# InputConn.net
KiCad netlist of a schematic drawn in Altium Designer
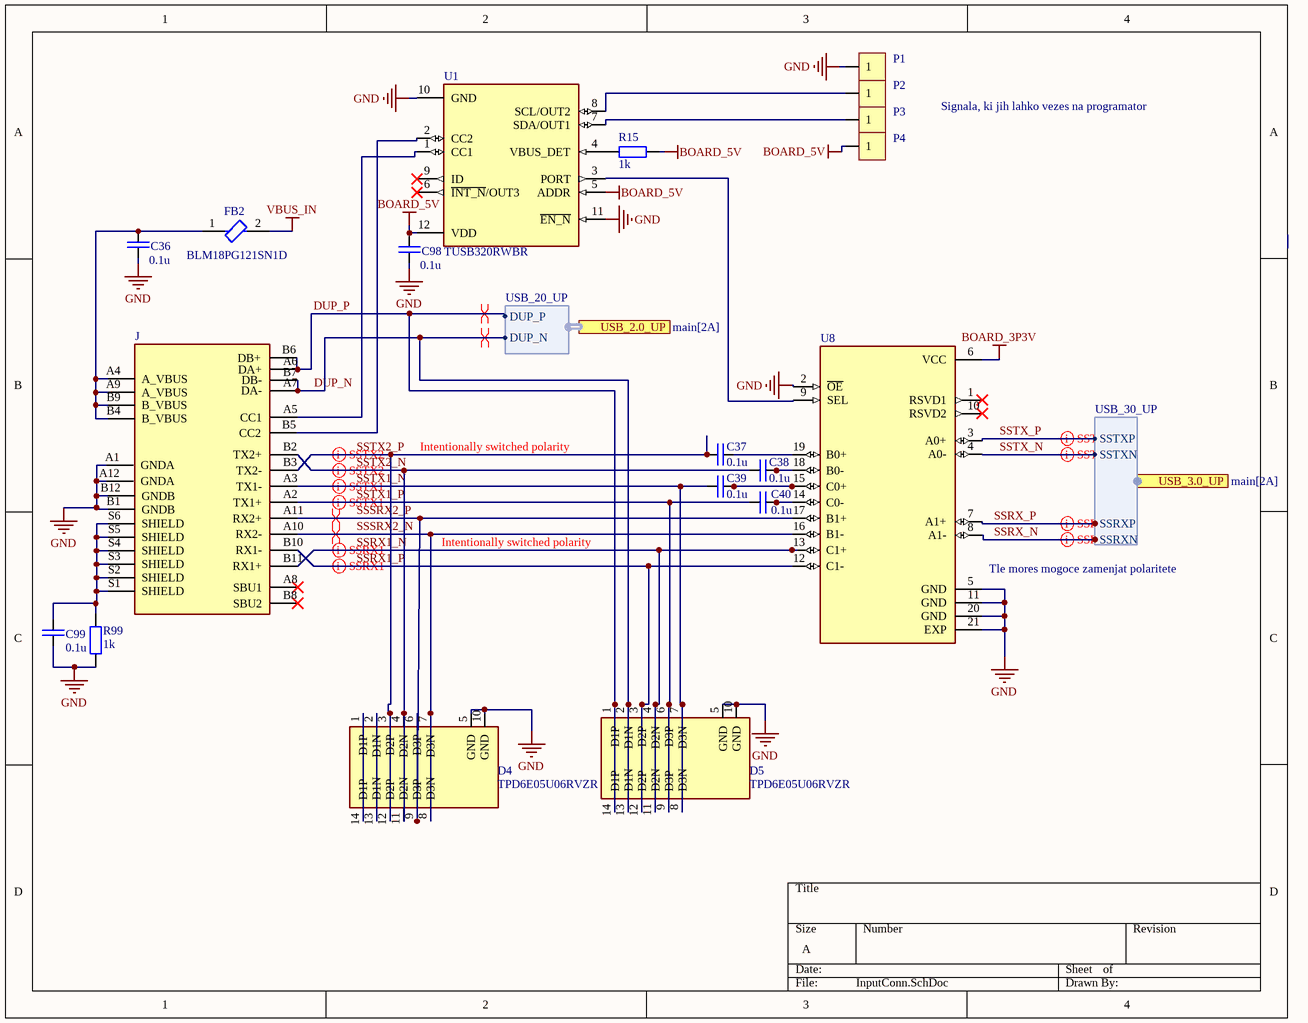
[diagram p0: InputConn.SchDoc]

(export (version "E")
  (design (tool "Eeschema 10.0.6"))
  (components
    (comp (ref "C36")
      (value "0.1u")
      (footprint "CAP_0603_N")
      (fields (field (name "Comment") "comment"))
      (libsource (lib "USB-HUB1") (part "Capacitor non-polarized"))
    )
    (comp (ref "C37")
      (value "0.1u")
      (footprint "CAP_0603_N")
      (fields (field (name "Comment") "comment"))
      (libsource (lib "USB-HUB1") (part "Capacitor non-polarized"))
    )
    (comp (ref "C38")
      (value "0.1u")
      (footprint "CAP_0603_N")
      (fields (field (name "Comment") "comment"))
      (libsource (lib "USB-HUB1") (part "Capacitor non-polarized"))
    )
    (comp (ref "C39")
      (value "0.1u")
      (footprint "CAP_0603_N")
      (fields (field (name "Comment") "comment"))
      (libsource (lib "USB-HUB1") (part "Capacitor non-polarized"))
    )
    (comp (ref "C40")
      (value "0.1u")
      (footprint "CAP_0603_N")
      (fields (field (name "Comment") "comment"))
      (libsource (lib "USB-HUB1") (part "Capacitor non-polarized"))
    )
    (comp (ref "C98")
      (value "0.1u")
      (footprint "CAP_0603_N")
      (fields (field (name "Comment") "comment"))
      (libsource (lib "USB-HUB1") (part "Capacitor non-polarized"))
    )
    (comp (ref "C99")
      (value "0.1u")
      (footprint "CAP_0603_N")
      (fields (field (name "Comment") "comment"))
      (libsource (lib "USB-HUB1") (part "Capacitor non-polarized"))
    )
    (comp (ref "D4")
      (value "TPD6E05U06RVZR")
      (footprint "SON50P135X350X55-14N")
      (description "6-Channel Ultra low capacitance IEC ESD protection diodes 14-USON -40 to 125")
      (libsource (lib "USB-HUB1") (part "TPD6E05U06RVZR"))
    )
    (comp (ref "D5")
      (value "TPD6E05U06RVZR")
      (footprint "SON50P135X350X55-14N")
      (description "6-Channel Ultra low capacitance IEC ESD protection diodes 14-USON -40 to 125")
      (libsource (lib "USB-HUB1") (part "TPD6E05U06RVZR"))
    )
    (comp (ref "FB2")
      (value "BLM18PG121SN1D")
      (footprint "FP-BLM18-0_15-t0_8-IPC_B")
      (description "Chip Ferrite Bead, 0603, 120Ω @ 100MHz, 0.05Ω, 25%, 2A")
      (fields (field (name "TOLERANCE") "25%"))
      (libsource (lib "Altium Content Vault") (part "5f30dd21d616792df468990f7003faa"))
    )
    (comp (ref "J")
      (value "~")
      (footprint "JAE_DX07B024JJ3R1600")
      (fields (field (name "MP") "DX07B024JJ3R1600") (field (name "MF") "JAE Electronics"))
      (libsource (lib "USB-HUB1") (part "DX07B024JJ3R1600"))
    )
    (comp (ref "P1") (value "H1x1") (footprint "HDR1X1") (libsource (lib "USB-HUB1") (part "Header 1X1")))
    (comp (ref "P2") (value "H1x1") (footprint "HDR1X1") (libsource (lib "USB-HUB1") (part "Header 1X1")))
    (comp (ref "P3") (value "H1x1") (footprint "HDR1X1") (libsource (lib "USB-HUB1") (part "Header 1X1")))
    (comp (ref "P4") (value "H1x1") (footprint "HDR1X1") (libsource (lib "USB-HUB1") (part "Header 1X1")))
    (comp (ref "R15")
      (value "1k")
      (footprint "SMD_0603_N")
      (fields (field (name "Comment") "comment"))
      (libsource (lib "USB-HUB1") (part "Resistor"))
    )
    (comp (ref "R99")
      (value "1k")
      (footprint "SMD_0603_N")
      (fields (field (name "Comment") "comment"))
      (libsource (lib "USB-HUB1") (part "Resistor"))
    )
    (comp (ref "U1")
      (value "TUSB320RWBR")
      (footprint "IC_TUSB320RWBR")
      (description "USB Type-C configuration channel logic and port control")
      (fields (field (name "MF") "Texas Instruments"))
      (libsource (lib "USB-HUB1") (part "TUSB320RWBR"))
    )
    (comp (ref "U8")
      (value "~")
      (footprint "QFN50P450X250X100-21N")
      (description "USB Switch IC 2 Channel 20-VQFN _4.5x2.5_")
      (fields (field (name "MF") "Texas Instruments") (field (name "MP") "HD3SS3212RKSR"))
      (libsource (lib "USB-HUB1") (part "HD3SS3212RKSR"))
    )
  )
  (nets
    (net (code "3") (name "/DUP_N") (class "Default")
      (node (ref "D5") (pin "13") (pinfunction "D1N_13") (pintype "bidirectional"))
      (node (ref "D5") (pin "2") (pinfunction "D1N_2") (pintype "bidirectional"))
      (node (ref "J") (pin "A7") (pinfunction "DA-_A7") (pintype "passive"))
      (node (ref "J") (pin "B7") (pinfunction "DB-_B7") (pintype "passive"))
    )
    (net (code "4") (name "/DUP_P") (class "Default")
      (node (ref "D5") (pin "1") (pinfunction "D1P_1") (pintype "bidirectional"))
      (node (ref "D5") (pin "14") (pinfunction "D1P_14") (pintype "bidirectional"))
      (node (ref "J") (pin "A6") (pinfunction "__DA+_A6") (pintype "passive"))
      (node (ref "J") (pin "B6") (pinfunction "DB+_B6") (pintype "passive"))
    )
    (net (code "5") (name "/SSRX1_N") (class "Default")
      (node (ref "D5") (pin "11") (pinfunction "D2N_11") (pintype "bidirectional"))
      (node (ref "D5") (pin "4") (pinfunction "D2N_4") (pintype "bidirectional"))
      (node (ref "J") (pin "B11") (pinfunction "RX1+_B11") (pintype "passive"))
      (node (ref "U8") (pin "13") (pinfunction "C1+_13") (pintype "bidirectional"))
    )
    (net (code "6") (name "/SSRX1_P") (class "Default")
      (node (ref "D5") (pin "12") (pinfunction "D2P_12") (pintype "bidirectional"))
      (node (ref "D5") (pin "3") (pinfunction "D2P_3") (pintype "bidirectional"))
      (node (ref "J") (pin "B10") (pinfunction "RX1-_B10") (pintype "passive"))
      (node (ref "U8") (pin "12") (pinfunction "C1-_12") (pintype "bidirectional"))
    )
    (net (code "7") (name "/SSRX_N") (class "Default")
      (node (ref "U8") (pin "8") (pinfunction "A1-_8") (pintype "bidirectional"))
    )
    (net (code "8") (name "/SSRX_P") (class "Default")
      (node (ref "U8") (pin "7") (pinfunction "A1+_7") (pintype "bidirectional"))
    )
    (net (code "9") (name "/SSSRX2_N") (class "Default")
      (node (ref "D4") (pin "7") (pinfunction "D3N_7") (pintype "bidirectional"))
      (node (ref "D4") (pin "8") (pinfunction "D3N_8") (pintype "bidirectional"))
      (node (ref "J") (pin "A10") (pinfunction "RX2-_A10") (pintype "passive"))
      (node (ref "U8") (pin "16") (pinfunction "B1-_16") (pintype "bidirectional"))
    )
    (net (code "10") (name "/SSSRX2_P") (class "Default")
      (node (ref "D4") (pin "6") (pinfunction "D3P_6") (pintype "bidirectional"))
      (node (ref "D4") (pin "9") (pinfunction "D3P_9") (pintype "bidirectional"))
      (node (ref "J") (pin "A11") (pinfunction "RX2+_A11") (pintype "passive"))
      (node (ref "U8") (pin "17") (pinfunction "B1+_17") (pintype "bidirectional"))
    )
    (net (code "11") (name "/SSTX1_N") (class "Default")
      (node (ref "C39") (pin "1") (pinfunction "1_1") (pintype "passive"))
      (node (ref "D5") (pin "7") (pinfunction "D3N_7") (pintype "bidirectional"))
      (node (ref "D5") (pin "8") (pinfunction "D3N_8") (pintype "bidirectional"))
      (node (ref "J") (pin "A3") (pinfunction "TX1-_A3") (pintype "passive"))
    )
    (net (code "12") (name "/SSTX1_P") (class "Default")
      (node (ref "C40") (pin "1") (pinfunction "1_1") (pintype "passive"))
      (node (ref "D5") (pin "6") (pinfunction "D3P_6") (pintype "bidirectional"))
      (node (ref "D5") (pin "9") (pinfunction "D3P_9") (pintype "bidirectional"))
      (node (ref "J") (pin "A2") (pinfunction "TX1+_A2") (pintype "passive"))
    )
    (net (code "13") (name "/SSTX2_N") (class "Default")
      (node (ref "C38") (pin "1") (pinfunction "1_1") (pintype "passive"))
      (node (ref "D4") (pin "11") (pinfunction "D2N_11") (pintype "bidirectional"))
      (node (ref "D4") (pin "4") (pinfunction "D2N_4") (pintype "bidirectional"))
      (node (ref "J") (pin "B2") (pinfunction "TX2+_B2") (pintype "passive"))
    )
    (net (code "14") (name "/SSTX2_P") (class "Default")
      (node (ref "C37") (pin "1") (pinfunction "1_1") (pintype "passive"))
      (node (ref "D4") (pin "12") (pinfunction "D2P_12") (pintype "bidirectional"))
      (node (ref "D4") (pin "3") (pinfunction "D2P_3") (pintype "bidirectional"))
      (node (ref "J") (pin "B3") (pinfunction "TX2-_B3") (pintype "passive"))
    )
    (net (code "15") (name "/SSTX_N") (class "Default")
      (node (ref "U8") (pin "4") (pinfunction "A0-_4") (pintype "bidirectional"))
    )
    (net (code "16") (name "/SSTX_P") (class "Default")
      (node (ref "U8") (pin "3") (pinfunction "A0+_3") (pintype "bidirectional"))
    )
    (net (code "19") (name "BOARD_3P3V") (class "Default")
      (node (ref "U8") (pin "6") (pinfunction "VCC_6") (pintype "power_in"))
    )
    (net (code "20") (name "BOARD_5V") (class "Default")
      (node (ref "C98") (pin "1") (pinfunction "1_1") (pintype "passive"))
      (node (ref "P4") (pin "1") (pinfunction "1_1") (pintype "passive"))
      (node (ref "R15") (pin "2") (pintype "passive"))
      (node (ref "U1") (pin "12") (pinfunction "VDD_12") (pintype "power_in"))
      (node (ref "U1") (pin "5") (pinfunction "ADDR_5") (pintype "input"))
    )
    (net (code "21") (name "GND") (class "Default")
      (node (ref "C36") (pin "2") (pinfunction "2_2") (pintype "passive"))
      (node (ref "C98") (pin "2") (pinfunction "2_2") (pintype "passive"))
      (node (ref "C99") (pin "1") (pinfunction "1_1") (pintype "passive"))
      (node (ref "D4") (pin "10") (pinfunction "GND_10") (pintype "power_in"))
      (node (ref "D4") (pin "5") (pinfunction "GND_5") (pintype "power_in"))
      (node (ref "D5") (pin "10") (pinfunction "GND_10") (pintype "power_in"))
      (node (ref "D5") (pin "5") (pinfunction "GND_5") (pintype "power_in"))
      (node (ref "J") (pin "A1") (pinfunction "GNDA_A1") (pintype "passive"))
      (node (ref "J") (pin "A12") (pinfunction "GNDA_A12") (pintype "passive"))
      (node (ref "J") (pin "B1") (pinfunction "GNDB_B1") (pintype "passive"))
      (node (ref "J") (pin "B12") (pinfunction "GNDB_B12") (pintype "passive"))
      (node (ref "P1") (pin "1") (pinfunction "1_1") (pintype "passive"))
      (node (ref "R99") (pin "1") (pintype "passive"))
      (node (ref "U1") (pin "10") (pinfunction "GND_10") (pintype "power_in"))
      (node (ref "U1") (pin "11") (pinfunction "~{EN_N}_11") (pintype "input"))
      (node (ref "U8") (pin "11") (pinfunction "GND_11") (pintype "power_in"))
      (node (ref "U8") (pin "2") (pinfunction "~{OE}_2") (pintype "input"))
      (node (ref "U8") (pin "20") (pinfunction "GND_20") (pintype "power_in"))
      (node (ref "U8") (pin "21") (pinfunction "EXP_21") (pintype "power_in"))
      (node (ref "U8") (pin "5") (pinfunction "GND_5") (pintype "power_in"))
    )
    (net (code "22") (name "Net-(C36-Pad1)") (class "Default")
      (node (ref "C36") (pin "1") (pinfunction "1_1") (pintype "passive"))
      (node (ref "FB2") (pin "1") (pinfunction "1_1") (pintype "passive"))
      (node (ref "J") (pin "A4") (pinfunction "A_VBUS_A4") (pintype "passive"))
      (node (ref "J") (pin "A9") (pinfunction "A_VBUS_A9") (pintype "passive"))
      (node (ref "J") (pin "B4") (pinfunction "B_VBUS_B4") (pintype "passive"))
      (node (ref "J") (pin "B9") (pinfunction "B_VBUS_B9") (pintype "passive"))
    )
    (net (code "23") (name "Net-(C99-Pad2)") (class "Default")
      (node (ref "C99") (pin "2") (pinfunction "2_2") (pintype "passive"))
      (node (ref "J") (pin "S1") (pinfunction "SHIELD_S1") (pintype "power_in"))
      (node (ref "J") (pin "S2") (pinfunction "SHIELD_S2") (pintype "power_in"))
      (node (ref "J") (pin "S3") (pinfunction "SHIELD_S3") (pintype "power_in"))
      (node (ref "J") (pin "S4") (pinfunction "SHIELD_S4") (pintype "power_in"))
      (node (ref "J") (pin "S5") (pinfunction "SHIELD_S5") (pintype "power_in"))
      (node (ref "J") (pin "S6") (pinfunction "SHIELD_S6") (pintype "power_in"))
      (node (ref "R99") (pin "2") (pintype "passive"))
    )
    (net (code "24") (name "Net-(D4-D1N-Pad13)") (class "Default")
      (node (ref "D4") (pin "13") (pinfunction "D1N_13") (pintype "bidirectional"))
      (node (ref "D4") (pin "2") (pinfunction "D1N_2") (pintype "bidirectional"))
    )
    (net (code "25") (name "Net-(D4-D1P-Pad1)") (class "Default")
      (node (ref "D4") (pin "1") (pinfunction "D1P_1") (pintype "bidirectional"))
      (node (ref "D4") (pin "14") (pinfunction "D1P_14") (pintype "bidirectional"))
    )
    (net (code "26") (name "Net-(J-CC1)") (class "Default")
      (node (ref "J") (pin "A5") (pinfunction "CC1_A5") (pintype "passive"))
      (node (ref "U1") (pin "1") (pinfunction "CC1_1") (pintype "bidirectional"))
    )
    (net (code "27") (name "Net-(J-CC2)") (class "Default")
      (node (ref "J") (pin "B5") (pinfunction "CC2_B5") (pintype "passive"))
      (node (ref "U1") (pin "2") (pinfunction "CC2_2") (pintype "bidirectional"))
    )
    (net (code "28") (name "Net-(U1-PORT)") (class "Default")
      (node (ref "U1") (pin "3") (pinfunction "PORT_3") (pintype "output"))
      (node (ref "U8") (pin "9") (pinfunction "SEL_9") (pintype "input"))
    )
    (net (code "29") (name "Net-(U1-SCL{slash}OUT2)") (class "Default")
      (node (ref "P2") (pin "1") (pinfunction "1_1") (pintype "passive"))
      (node (ref "U1") (pin "8") (pinfunction "SCL/OUT2_8") (pintype "bidirectional"))
    )
    (net (code "30") (name "Net-(U1-SDA{slash}OUT1)") (class "Default")
      (node (ref "P3") (pin "1") (pinfunction "1_1") (pintype "passive"))
      (node (ref "U1") (pin "7") (pinfunction "SDA/OUT1_7") (pintype "bidirectional"))
    )
    (net (code "31") (name "Net-(U1-VBUS_DET)") (class "Default")
      (node (ref "R15") (pin "1") (pintype "passive"))
      (node (ref "U1") (pin "4") (pinfunction "VBUS_DET_4") (pintype "input"))
    )
    (net (code "32") (name "Net-(U8-B0+)") (class "Default")
      (node (ref "C37") (pin "2") (pinfunction "2_2") (pintype "passive"))
      (node (ref "U8") (pin "19") (pinfunction "B0+_19") (pintype "bidirectional"))
    )
    (net (code "33") (name "Net-(U8-B0-)") (class "Default")
      (node (ref "C38") (pin "2") (pinfunction "2_2") (pintype "passive"))
      (node (ref "U8") (pin "18") (pinfunction "B0-_18") (pintype "bidirectional"))
    )
    (net (code "34") (name "Net-(U8-C0+)") (class "Default")
      (node (ref "C39") (pin "2") (pinfunction "2_2") (pintype "passive"))
      (node (ref "U8") (pin "15") (pinfunction "C0+_15") (pintype "bidirectional"))
    )
    (net (code "35") (name "Net-(U8-C0-)") (class "Default")
      (node (ref "C40") (pin "2") (pinfunction "2_2") (pintype "passive"))
      (node (ref "U8") (pin "14") (pinfunction "C0-_14") (pintype "bidirectional"))
    )
    (net (code "36") (name "VBUS_IN") (class "Default")
      (node (ref "FB2") (pin "2") (pinfunction "2_2") (pintype "passive"))
    )
    (net (code "37") (name "unconnected-(J-SBU1-PadA8)") (class "Default")
      (node (ref "J") (pin "A8") (pinfunction "SBU1_A8") (pintype "passive+no_connect"))
    )
    (net (code "38") (name "unconnected-(J-SBU2-PadB8)") (class "Default")
      (node (ref "J") (pin "B8") (pinfunction "SBU2_B8") (pintype "passive+no_connect"))
    )
    (net (code "39") (name "unconnected-(U1-ID-Pad9)") (class "Default")
      (node (ref "U1") (pin "9") (pinfunction "ID_9") (pintype "output+no_connect"))
    )
    (net (code "40") (name "unconnected-(U1-~{INT_N}{slash}OUT3-Pad6)") (class "Default")
      (node (ref "U1") (pin "6") (pinfunction "~{INT_N}/OUT3_6") (pintype "output+no_connect"))
    )
    (net (code "41") (name "unconnected-(U8-RSVD1-Pad1)") (class "Default")
      (node (ref "U8") (pin "1") (pinfunction "RSVD1_1") (pintype "output+no_connect"))
    )
    (net (code "42") (name "unconnected-(U8-RSVD2-Pad10)") (class "Default")
      (node (ref "U8") (pin "10") (pinfunction "RSVD2_10") (pintype "output+no_connect"))
    )
  )
)
